# STM32F407IGH6BGA.net
KiCad netlist of a schematic drawn in Altium Designer
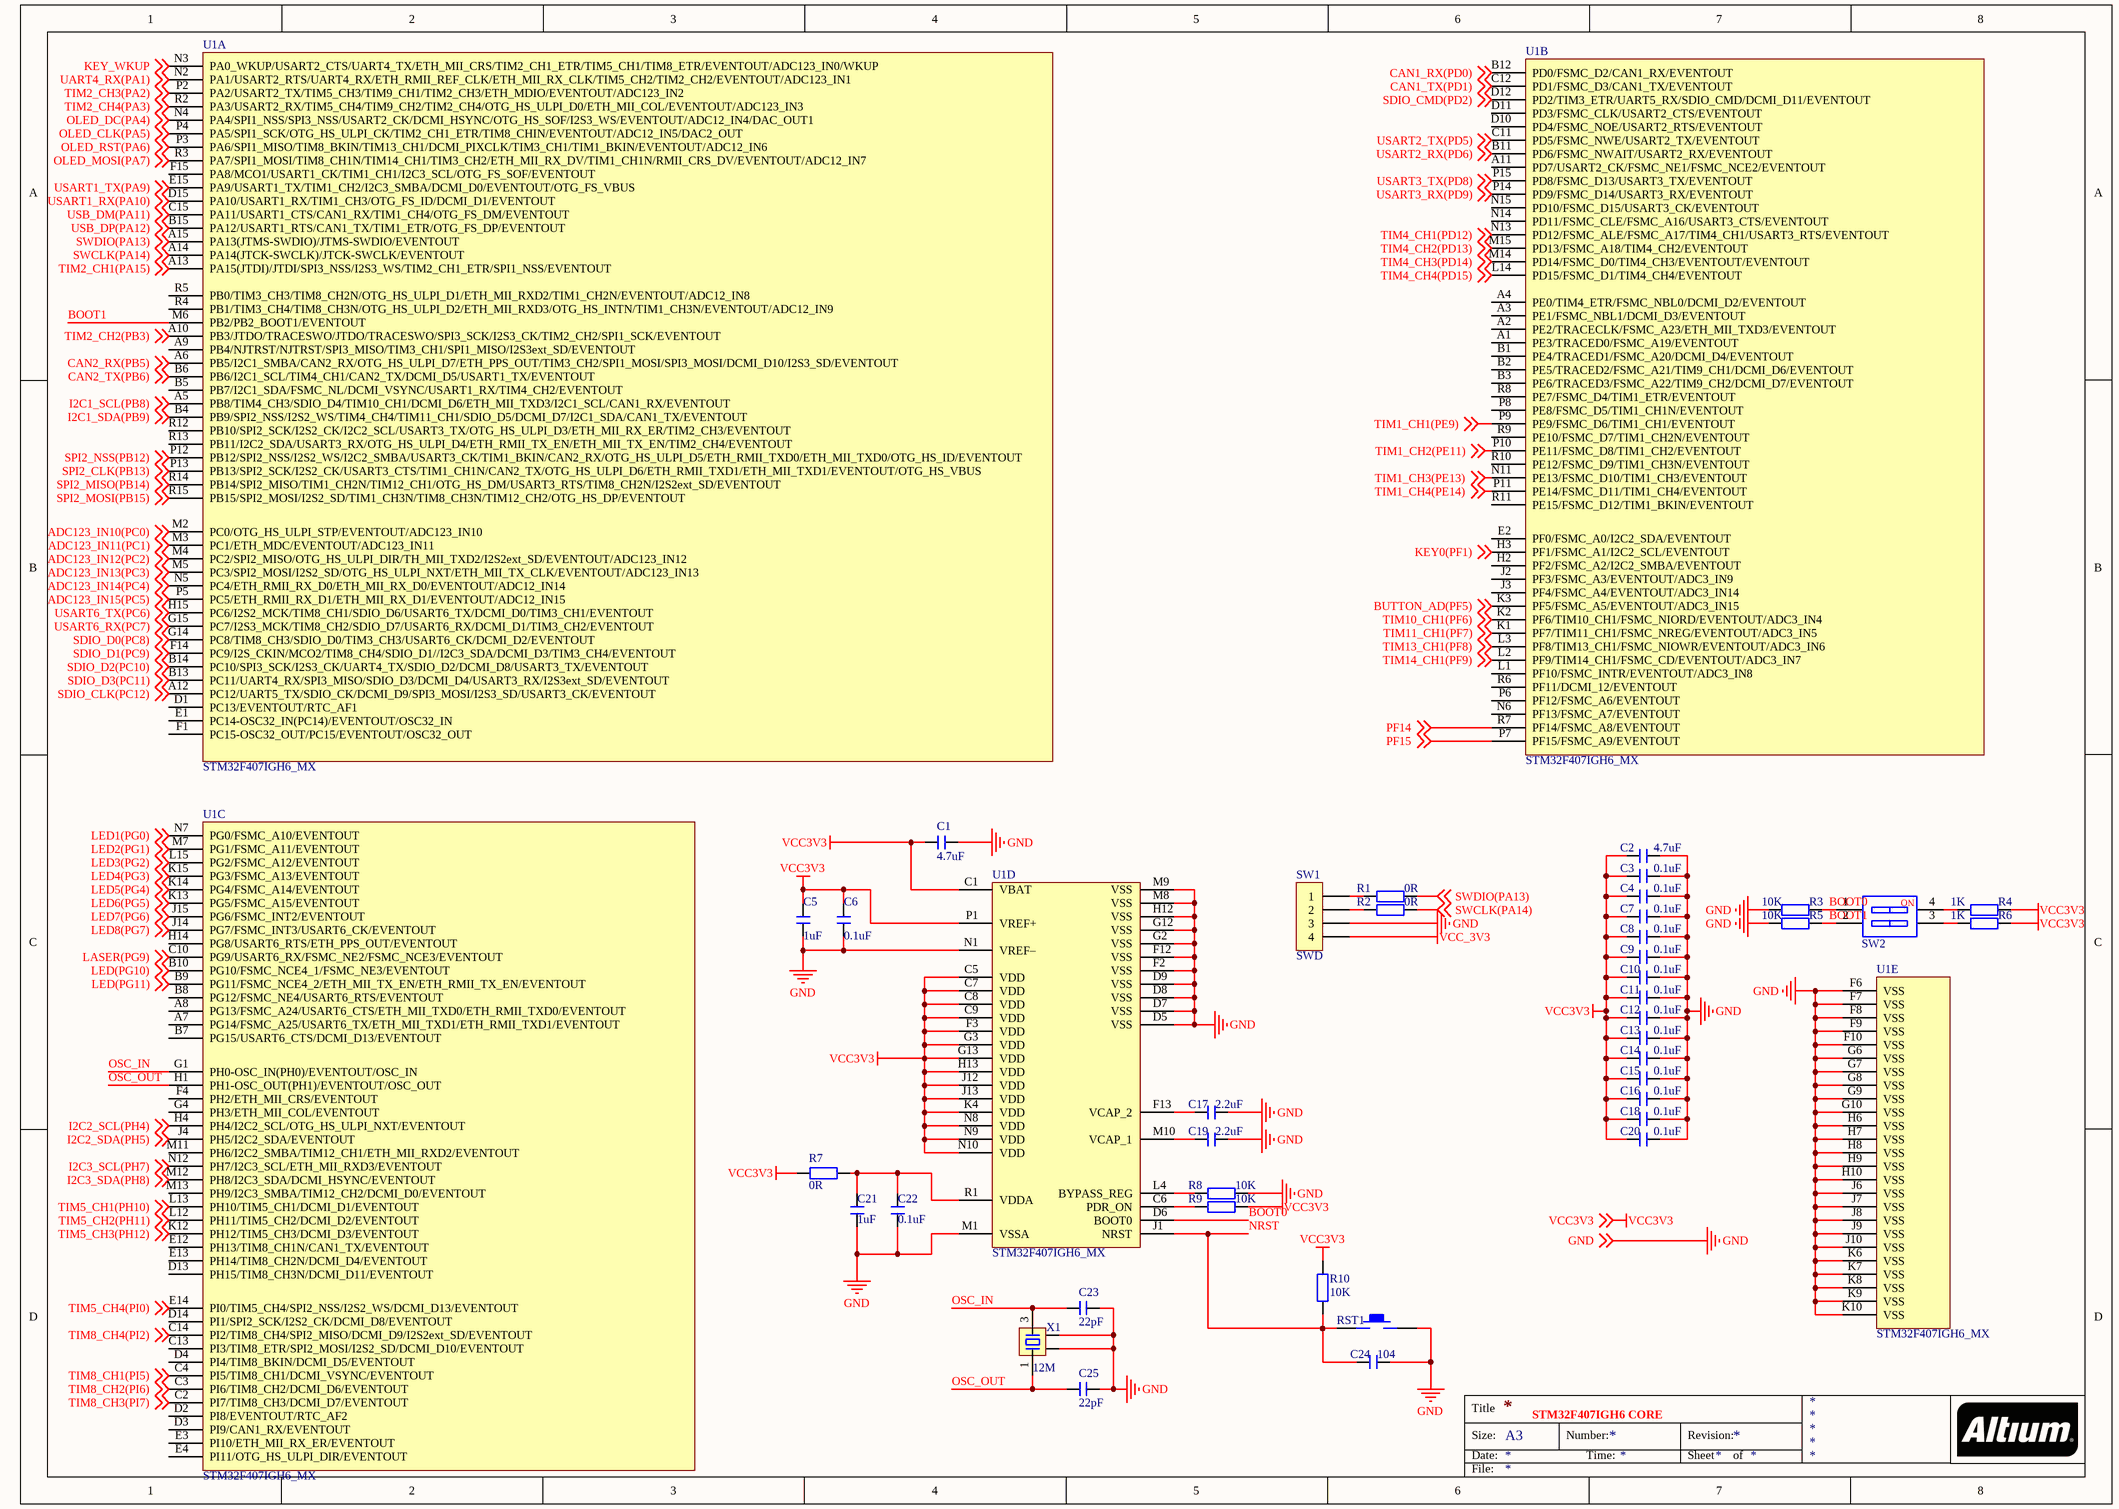
[diagram p0: STM32F407IGH6BGA.SchDoc]

(export (version "E")
  (design (tool "Eeschema 10.0.6"))
  (components
    (comp (ref "C1")
      (value "4.7uF")
      (footprint "C 0402_M")
      (description "贴片电容")
      (libsource (lib "0.1 - 电阻-电容-电感") (part "C"))
    )
    (comp (ref "C2")
      (value "4.7uF")
      (footprint "C 0402_M")
      (description "贴片电容")
      (libsource (lib "0.1 - 电阻-电容-电感") (part "C"))
    )
    (comp (ref "C3")
      (value "0.1uF")
      (footprint "C 0402_M")
      (description "贴片电容")
      (libsource (lib "0.1 - 电阻-电容-电感") (part "C"))
    )
    (comp (ref "C4")
      (value "0.1uF")
      (footprint "C 0402_M")
      (description "贴片电容")
      (libsource (lib "0.1 - 电阻-电容-电感") (part "C"))
    )
    (comp (ref "C5")
      (value "1uF")
      (footprint "C 0402_M")
      (description "贴片电容")
      (libsource (lib "0.1 - 电阻-电容-电感") (part "C"))
    )
    (comp (ref "C6")
      (value "0.1uF")
      (footprint "C 0402_M")
      (description "贴片电容")
      (libsource (lib "0.1 - 电阻-电容-电感") (part "C"))
    )
    (comp (ref "C7")
      (value "0.1uF")
      (footprint "C 0402_M")
      (description "贴片电容")
      (libsource (lib "0.1 - 电阻-电容-电感") (part "C"))
    )
    (comp (ref "C8")
      (value "0.1uF")
      (footprint "C 0402_M")
      (description "贴片电容")
      (libsource (lib "0.1 - 电阻-电容-电感") (part "C"))
    )
    (comp (ref "C9")
      (value "0.1uF")
      (footprint "C 0402_M")
      (description "贴片电容")
      (libsource (lib "0.1 - 电阻-电容-电感") (part "C"))
    )
    (comp (ref "C10")
      (value "0.1uF")
      (footprint "C 0402_M")
      (description "贴片电容")
      (libsource (lib "0.1 - 电阻-电容-电感") (part "C"))
    )
    (comp (ref "C11")
      (value "0.1uF")
      (footprint "C 0402_M")
      (description "贴片电容")
      (libsource (lib "0.1 - 电阻-电容-电感") (part "C"))
    )
    (comp (ref "C12")
      (value "0.1uF")
      (footprint "C 0402_M")
      (description "贴片电容")
      (libsource (lib "0.1 - 电阻-电容-电感") (part "C"))
    )
    (comp (ref "C13")
      (value "0.1uF")
      (footprint "C 0402_M")
      (description "贴片电容")
      (libsource (lib "0.1 - 电阻-电容-电感") (part "C"))
    )
    (comp (ref "C14")
      (value "0.1uF")
      (footprint "C 0402_M")
      (description "贴片电容")
      (libsource (lib "0.1 - 电阻-电容-电感") (part "C"))
    )
    (comp (ref "C15")
      (value "0.1uF")
      (footprint "C 0402_M")
      (description "贴片电容")
      (libsource (lib "0.1 - 电阻-电容-电感") (part "C"))
    )
    (comp (ref "C16")
      (value "0.1uF")
      (footprint "C 0402_M")
      (description "贴片电容")
      (libsource (lib "0.1 - 电阻-电容-电感") (part "C"))
    )
    (comp (ref "C17")
      (value "2.2uF")
      (footprint "C 0402_M")
      (description "贴片电容")
      (libsource (lib "0.1 - 电阻-电容-电感") (part "C"))
    )
    (comp (ref "C18")
      (value "0.1uF")
      (footprint "C 0402_M")
      (description "贴片电容")
      (libsource (lib "0.1 - 电阻-电容-电感") (part "C"))
    )
    (comp (ref "C19")
      (value "2.2uF")
      (footprint "C 0402_M")
      (description "贴片电容")
      (libsource (lib "0.1 - 电阻-电容-电感") (part "C"))
    )
    (comp (ref "C20")
      (value "0.1uF")
      (footprint "C 0402_M")
      (description "贴片电容")
      (libsource (lib "0.1 - 电阻-电容-电感") (part "C"))
    )
    (comp (ref "C21")
      (value "1uF")
      (footprint "C 0402_M")
      (description "贴片电容")
      (libsource (lib "0.1 - 电阻-电容-电感") (part "C"))
    )
    (comp (ref "C22")
      (value "0.1uF")
      (footprint "C 0402_M")
      (description "贴片电容")
      (libsource (lib "0.1 - 电阻-电容-电感") (part "C"))
    )
    (comp (ref "C23")
      (value "22pF")
      (footprint "C 0402_M")
      (description "贴片电容")
      (libsource (lib "0.1 - 电阻-电容-电感") (part "C"))
    )
    (comp (ref "C24")
      (value "104")
      (footprint "C 0402_M")
      (description "贴片电容")
      (libsource (lib "0.1 - 电阻-电容-电感") (part "C"))
    )
    (comp (ref "C25")
      (value "22pF")
      (footprint "C 0402_M")
      (description "贴片电容")
      (libsource (lib "0.1 - 电阻-电容-电感") (part "C"))
    )
    (comp (ref "R1")
      (value "0R")
      (footprint "R 0402_M")
      (description "贴片电阻")
      (libsource (lib "0.1 - 电阻-电容-电感") (part "R"))
    )
    (comp (ref "R2")
      (value "0R")
      (footprint "R 0402_M")
      (description "贴片电阻")
      (libsource (lib "0.1 - 电阻-电容-电感") (part "R"))
    )
    (comp (ref "R3")
      (value "10K")
      (footprint "R 0402_M")
      (description "贴片电阻")
      (libsource (lib "0.1 - 电阻-电容-电感") (part "R"))
    )
    (comp (ref "R4")
      (value "1K")
      (footprint "R 0402_M")
      (description "贴片电阻")
      (libsource (lib "0.1 - 电阻-电容-电感") (part "R"))
    )
    (comp (ref "R5")
      (value "10K")
      (footprint "R 0402_M")
      (description "贴片电阻")
      (libsource (lib "0.1 - 电阻-电容-电感") (part "R"))
    )
    (comp (ref "R6")
      (value "1K")
      (footprint "R 0402_M")
      (description "贴片电阻")
      (libsource (lib "0.1 - 电阻-电容-电感") (part "R"))
    )
    (comp (ref "R7")
      (value "0R")
      (footprint "R 0402_M")
      (description "贴片电阻")
      (libsource (lib "0.1 - 电阻-电容-电感") (part "R"))
    )
    (comp (ref "R8")
      (value "10K")
      (footprint "R 0402_M")
      (description "贴片电阻")
      (libsource (lib "0.1 - 电阻-电容-电感") (part "R"))
    )
    (comp (ref "R9")
      (value "10K")
      (footprint "R 0402_M")
      (description "贴片电阻")
      (libsource (lib "0.1 - 电阻-电容-电感") (part "R"))
    )
    (comp (ref "R10")
      (value "10K")
      (footprint "R 0402_M")
      (description "贴片电阻")
      (libsource (lib "0.1 - 电阻-电容-电感") (part "R"))
    )
    (comp (ref "RST1")
      (value "RST")
      (footprint "mx_pcb_library:SMD-3.2*4.2")
      (libsource (lib "mx_pcb_library") (part "KEY_M"))
    )
    (comp (ref "SW1")
      (value "SWD")
      (footprint "4.50-MX1.25连接器:MX 1.25-WS-4P")
      (description "Connector")
      (libsource (lib "mx_pcb_library") (part "HDR1x4"))
    )
    (comp (ref "SW2")
      (value "SW-2P")
      (footprint "CSW1.27 SMD-2P")
      (description "2路编码开关")
      (libsource (lib "0.7 - 常用按键-开关") (part "SW-2P"))
    )
    (comp (ref "U1")
      (value "STM32F407IGH6_MX")
      (footprint "mx_pcb_library:UBGA-176+25")
      (libsource (lib "mx_pcb_library") (part "STM32F407IGH6_MX"))
    )
    (comp (ref "X1")
      (value "12M")
      (footprint "OSC 3225-4P")
      (description "4脚无源晶振")
      (libsource (lib "2.0 - 保险丝-晶振-光耦") (part "XTAL-4P"))
    )
  )
  (nets
    (net (code "1") (name "/BOOT0") (class "Default")
      (node (ref "R3") (pin "2") (pinfunction "2_2") (pintype "passive"))
      (node (ref "SW2") (pin "1") (pinfunction "1_1") (pintype "passive"))
      (node (ref "U1") (pin "D6") (pinfunction "BOOT0_D6") (pintype "passive"))
    )
    (net (code "2") (name "/BOOT1") (class "Default")
      (node (ref "R5") (pin "2") (pinfunction "2_2") (pintype "passive"))
      (node (ref "SW2") (pin "2") (pinfunction "2_2") (pintype "passive"))
      (node (ref "U1") (pin "M6") (pinfunction "PB2/PB2_BOOT1/EVENTOUT_M6") (pintype "passive"))
    )
    (net (code "3") (name "/NRST") (class "Default")
      (node (ref "C24") (pin "1") (pinfunction "1_1") (pintype "passive"))
      (node (ref "R10") (pin "1") (pinfunction "1_1") (pintype "passive"))
      (node (ref "RST1") (pin "1") (pinfunction "1_1") (pintype "passive"))
      (node (ref "U1") (pin "J1") (pinfunction "NRST_J1") (pintype "passive"))
    )
    (net (code "4") (name "/OSC_IN") (class "Default")
      (node (ref "C23") (pin "1") (pinfunction "1_1") (pintype "passive"))
      (node (ref "U1") (pin "G1") (pinfunction "PH0-OSC_IN(PH0)/EVENTOUT/OSC_IN_G1") (pintype "passive"))
      (node (ref "X1") (pin "3") (pinfunction "3_3") (pintype "passive"))
    )
    (net (code "5") (name "/OSC_OUT") (class "Default")
      (node (ref "C25") (pin "1") (pinfunction "1_1") (pintype "passive"))
      (node (ref "U1") (pin "H1") (pinfunction "PH1-OSC_OUT(PH1)/EVENTOUT/OSC_OUT_H1") (pintype "passive"))
      (node (ref "X1") (pin "1") (pinfunction "1_1") (pintype "passive"))
    )
    (net (code "6") (name "ADC123_IN10(PC0)") (class "Default")
      (node (ref "U1") (pin "M2") (pinfunction "PC0/OTG_HS_ULPI_STP/EVENTOUT/ADC123_IN10_M2") (pintype "passive"))
    )
    (net (code "7") (name "ADC123_IN11(PC1)") (class "Default")
      (node (ref "U1") (pin "M3") (pinfunction "PC1/ETH_MDC/EVENTOUT/ADC123_IN11_M3") (pintype "passive"))
    )
    (net (code "8") (name "ADC123_IN12(PC2)") (class "Default")
      (node (ref "U1") (pin "M4") (pinfunction "PC2/SPI2_MISO/OTG_HS_ULPI_DIR/TH_MII_TXD2/I2S2ext_SD/EVENTOUT/ADC123_IN12_M4") (pintype "passive"))
    )
    (net (code "9") (name "ADC123_IN13(PC3)") (class "Default")
      (node (ref "U1") (pin "M5") (pinfunction "PC3/SPI2_MOSI/I2S2_SD/OTG_HS_ULPI_NXT/ETH_MII_TX_CLK/EVENTOUT/ADC123_IN13_M5") (pintype "passive"))
    )
    (net (code "10") (name "ADC123_IN14(PC4)") (class "Default")
      (node (ref "U1") (pin "N5") (pinfunction "PC4/ETH_RMII_RX_D0/ETH_MII_RX_D0/EVENTOUT/ADC12_IN14_N5") (pintype "passive"))
    )
    (net (code "11") (name "ADC123_IN15(PC5)") (class "Default")
      (node (ref "U1") (pin "P5") (pinfunction "PC5/ETH_RMII_RX_D1/ETH_MII_RX_D1/EVENTOUT/ADC12_IN15_P5") (pintype "passive"))
    )
    (net (code "12") (name "BUTTON_AD(PF5)") (class "Default")
      (node (ref "U1") (pin "K3") (pinfunction "PF5/FSMC_A5/EVENTOUT/ADC3_IN15_K3") (pintype "passive"))
    )
    (net (code "13") (name "CAN1_RX(PD0)") (class "Default")
      (node (ref "U1") (pin "B12") (pinfunction "PD0/FSMC_D2/CAN1_RX/EVENTOUT_B12") (pintype "passive"))
    )
    (net (code "14") (name "CAN1_TX(PD1)") (class "Default")
      (node (ref "U1") (pin "C12") (pinfunction "PD1/FSMC_D3/CAN1_TX/EVENTOUT_C12") (pintype "passive"))
    )
    (net (code "15") (name "CAN2_RX(PB5)") (class "Default")
      (node (ref "U1") (pin "A6") (pinfunction "PB5/I2C1_SMBA/CAN2_RX/OTG_HS_ULPI_D7/ETH_PPS_OUT/TIM3_CH2/SPI1_MOSI/SPI3_MOSI/DCMI_D10/I2S3_SD/EVENTOUT_A6") (pintype "passive"))
    )
    (net (code "16") (name "CAN2_TX(PB6)") (class "Default")
      (node (ref "U1") (pin "B6") (pinfunction "PB6/I2C1_SCL/TIM4_CH1/CAN2_TX/DCMI_D5/USART1_TX/EVENTOUT_B6") (pintype "passive"))
    )
    (net (code "17") (name "GND") (class "Default")
      (node (ref "C1") (pin "1") (pinfunction "1_1") (pintype "passive"))
      (node (ref "C10") (pin "2") (pinfunction "2_2") (pintype "passive"))
      (node (ref "C11") (pin "2") (pinfunction "2_2") (pintype "passive"))
      (node (ref "C12") (pin "2") (pinfunction "2_2") (pintype "passive"))
      (node (ref "C13") (pin "2") (pinfunction "2_2") (pintype "passive"))
      (node (ref "C14") (pin "2") (pinfunction "2_2") (pintype "passive"))
      (node (ref "C15") (pin "2") (pinfunction "2_2") (pintype "passive"))
      (node (ref "C16") (pin "2") (pinfunction "2_2") (pintype "passive"))
      (node (ref "C17") (pin "2") (pinfunction "2_2") (pintype "passive"))
      (node (ref "C18") (pin "2") (pinfunction "2_2") (pintype "passive"))
      (node (ref "C19") (pin "2") (pinfunction "2_2") (pintype "passive"))
      (node (ref "C2") (pin "2") (pinfunction "2_2") (pintype "passive"))
      (node (ref "C20") (pin "2") (pinfunction "2_2") (pintype "passive"))
      (node (ref "C21") (pin "1") (pinfunction "1_1") (pintype "passive"))
      (node (ref "C22") (pin "1") (pinfunction "1_1") (pintype "passive"))
      (node (ref "C23") (pin "2") (pinfunction "2_2") (pintype "passive"))
      (node (ref "C24") (pin "2") (pinfunction "2_2") (pintype "passive"))
      (node (ref "C25") (pin "2") (pinfunction "2_2") (pintype "passive"))
      (node (ref "C3") (pin "2") (pinfunction "2_2") (pintype "passive"))
      (node (ref "C4") (pin "2") (pinfunction "2_2") (pintype "passive"))
      (node (ref "C5") (pin "1") (pinfunction "1_1") (pintype "passive"))
      (node (ref "C6") (pin "1") (pinfunction "1_1") (pintype "passive"))
      (node (ref "C7") (pin "2") (pinfunction "2_2") (pintype "passive"))
      (node (ref "C8") (pin "2") (pinfunction "2_2") (pintype "passive"))
      (node (ref "C9") (pin "2") (pinfunction "2_2") (pintype "passive"))
      (node (ref "R3") (pin "1") (pinfunction "1_1") (pintype "passive"))
      (node (ref "R5") (pin "1") (pinfunction "1_1") (pintype "passive"))
      (node (ref "R8") (pin "2") (pinfunction "2_2") (pintype "passive"))
      (node (ref "RST1") (pin "2") (pinfunction "2_2") (pintype "passive"))
      (node (ref "SW1") (pin "3") (pinfunction "3_3") (pintype "passive"))
      (node (ref "U1") (pin "D5") (pinfunction "VSS_D5") (pintype "passive"))
      (node (ref "U1") (pin "D7") (pinfunction "VSS_D7") (pintype "passive"))
      (node (ref "U1") (pin "D8") (pinfunction "VSS_D8") (pintype "passive"))
      (node (ref "U1") (pin "D9") (pinfunction "VSS_D9") (pintype "passive"))
      (node (ref "U1") (pin "F10") (pinfunction "VSS_F10") (pintype "passive"))
      (node (ref "U1") (pin "F12") (pinfunction "VSS_F12") (pintype "passive"))
      (node (ref "U1") (pin "F2") (pinfunction "VSS_F2") (pintype "passive"))
      (node (ref "U1") (pin "F6") (pinfunction "VSS_F6") (pintype "passive"))
      (node (ref "U1") (pin "F7") (pinfunction "VSS_F7") (pintype "passive"))
      (node (ref "U1") (pin "F8") (pinfunction "VSS_F8") (pintype "passive"))
      (node (ref "U1") (pin "F9") (pinfunction "VSS_F9") (pintype "passive"))
      (node (ref "U1") (pin "G10") (pinfunction "VSS_G10") (pintype "passive"))
      (node (ref "U1") (pin "G12") (pinfunction "VSS_G12") (pintype "passive"))
      (node (ref "U1") (pin "G2") (pinfunction "VSS_G2") (pintype "passive"))
      (node (ref "U1") (pin "G6") (pinfunction "VSS_G6") (pintype "passive"))
      (node (ref "U1") (pin "G7") (pinfunction "VSS_G7") (pintype "passive"))
      (node (ref "U1") (pin "G8") (pinfunction "VSS_G8") (pintype "passive"))
      (node (ref "U1") (pin "G9") (pinfunction "VSS_G9") (pintype "passive"))
      (node (ref "U1") (pin "H10") (pinfunction "VSS_H10") (pintype "passive"))
      (node (ref "U1") (pin "H12") (pinfunction "VSS_H12") (pintype "passive"))
      (node (ref "U1") (pin "H6") (pinfunction "VSS_H6") (pintype "passive"))
      (node (ref "U1") (pin "H7") (pinfunction "VSS_H7") (pintype "passive"))
      (node (ref "U1") (pin "H8") (pinfunction "VSS_H8") (pintype "passive"))
      (node (ref "U1") (pin "H9") (pinfunction "VSS_H9") (pintype "passive"))
      (node (ref "U1") (pin "J10") (pinfunction "VSS_J10") (pintype "passive"))
      (node (ref "U1") (pin "J6") (pinfunction "VSS_J6") (pintype "passive"))
      (node (ref "U1") (pin "J7") (pinfunction "VSS_J7") (pintype "passive"))
      (node (ref "U1") (pin "J8") (pinfunction "VSS_J8") (pintype "passive"))
      (node (ref "U1") (pin "J9") (pinfunction "VSS_J9") (pintype "passive"))
      (node (ref "U1") (pin "K10") (pinfunction "VSS_K10") (pintype "passive"))
      (node (ref "U1") (pin "K6") (pinfunction "VSS_K6") (pintype "passive"))
      (node (ref "U1") (pin "K7") (pinfunction "VSS_K7") (pintype "passive"))
      (node (ref "U1") (pin "K8") (pinfunction "VSS_K8") (pintype "passive"))
      (node (ref "U1") (pin "K9") (pinfunction "VSS_K9") (pintype "passive"))
      (node (ref "U1") (pin "M1") (pinfunction "VSSA_M1") (pintype "passive"))
      (node (ref "U1") (pin "M8") (pinfunction "VSS_M8") (pintype "passive"))
      (node (ref "U1") (pin "M9") (pinfunction "VSS_M9") (pintype "passive"))
      (node (ref "U1") (pin "N1") (pinfunction "VREF–_N1") (pintype "passive"))
      (node (ref "X1") (pin "2") (pinfunction "2_2") (pintype "passive"))
      (node (ref "X1") (pin "4") (pinfunction "4_4") (pintype "passive"))
    )
    (net (code "18") (name "I2C1_SCL(PB8)") (class "Default")
      (node (ref "U1") (pin "A5") (pinfunction "PB8/TIM4_CH3/SDIO_D4/TIM10_CH1/DCMI_D6/ETH_MII_TXD3/I2C1_SCL/CAN1_RX/EVENTOUT_A5") (pintype "passive"))
    )
    (net (code "19") (name "I2C1_SDA(PB9)") (class "Default")
      (node (ref "U1") (pin "B4") (pinfunction "PB9/SPI2_NSS/I2S2_WS/TIM4_CH4/TIM11_CH1/SDIO_D5/DCMI_D7/I2C1_SDA/CAN1_TX/EVENTOUT_B4") (pintype "passive"))
    )
    (net (code "20") (name "I2C2_SCL(PH4)") (class "Default")
      (node (ref "U1") (pin "H4") (pinfunction "PH4/I2C2_SCL/OTG_HS_ULPI_NXT/EVENTOUT_H4") (pintype "passive"))
    )
    (net (code "21") (name "I2C2_SDA(PH5)") (class "Default")
      (node (ref "U1") (pin "J4") (pinfunction "PH5/I2C2_SDA/EVENTOUT_J4") (pintype "passive"))
    )
    (net (code "22") (name "I2C3_SCL(PH7)") (class "Default")
      (node (ref "U1") (pin "N12") (pinfunction "PH7/I2C3_SCL/ETH_MII_RXD3/EVENTOUT_N12") (pintype "passive"))
    )
    (net (code "23") (name "I2C3_SDA(PH8)") (class "Default")
      (node (ref "U1") (pin "M12") (pinfunction "PH8/I2C3_SDA/DCMI_HSYNC/EVENTOUT_M12") (pintype "passive"))
    )
    (net (code "24") (name "KEY0(PF1)") (class "Default")
      (node (ref "U1") (pin "H3") (pinfunction "PF1/FSMC_A1/I2C2_SCL/EVENTOUT_H3") (pintype "passive"))
    )
    (net (code "25") (name "KEY_WKUP") (class "Default")
      (node (ref "U1") (pin "N3") (pinfunction "PA0_WKUP/USART2_CTS/UART4_TX/ETH_MII_CRS/TIM2_CH1_ETR/TIM5_CH1/TIM8_ETR/EVENTOUT/ADC123_IN0/WKUP_N3") (pintype "passive"))
    )
    (net (code "26") (name "LASER(PG9)") (class "Default")
      (node (ref "U1") (pin "C10") (pinfunction "PG9/USART6_RX/FSMC_NE2/FSMC_NCE3/EVENTOUT_C10") (pintype "passive"))
    )
    (net (code "27") (name "LED(PG10)") (class "Default")
      (node (ref "U1") (pin "B10") (pinfunction "PG10/FSMC_NCE4_1/FSMC_NE3/EVENTOUT_B10") (pintype "passive"))
    )
    (net (code "28") (name "LED(PG11)") (class "Default")
      (node (ref "U1") (pin "B9") (pinfunction "PG11/FSMC_NCE4_2/ETH_MII_TX_EN/ETH_RMII_TX_EN/EVENTOUT_B9") (pintype "passive"))
    )
    (net (code "29") (name "LED1(PG0)") (class "Default")
      (node (ref "U1") (pin "N7") (pinfunction "PG0/FSMC_A10/EVENTOUT_N7") (pintype "passive"))
    )
    (net (code "30") (name "LED2(PG1)") (class "Default")
      (node (ref "U1") (pin "M7") (pinfunction "PG1/FSMC_A11/EVENTOUT_M7") (pintype "passive"))
    )
    (net (code "31") (name "LED3(PG2)") (class "Default")
      (node (ref "U1") (pin "L15") (pinfunction "PG2/FSMC_A12/EVENTOUT_L15") (pintype "passive"))
    )
    (net (code "32") (name "LED4(PG3)") (class "Default")
      (node (ref "U1") (pin "K15") (pinfunction "PG3/FSMC_A13/EVENTOUT_K15") (pintype "passive"))
    )
    (net (code "33") (name "LED5(PG4)") (class "Default")
      (node (ref "U1") (pin "K14") (pinfunction "PG4/FSMC_A14/EVENTOUT_K14") (pintype "passive"))
    )
    (net (code "34") (name "LED6(PG5)") (class "Default")
      (node (ref "U1") (pin "K13") (pinfunction "PG5/FSMC_A15/EVENTOUT_K13") (pintype "passive"))
    )
    (net (code "35") (name "LED7(PG6)") (class "Default")
      (node (ref "U1") (pin "J15") (pinfunction "PG6/FSMC_INT2/EVENTOUT_J15") (pintype "passive"))
    )
    (net (code "36") (name "LED8(PG7)") (class "Default")
      (node (ref "U1") (pin "J14") (pinfunction "PG7/FSMC_INT3/USART6_CK/EVENTOUT_J14") (pintype "passive"))
    )
    (net (code "37") (name "Net-(R1-Pad1)") (class "Default")
      (node (ref "R1") (pin "1") (pinfunction "1_1") (pintype "passive"))
      (node (ref "SW1") (pin "1") (pinfunction "1_1") (pintype "passive"))
    )
    (net (code "38") (name "Net-(R2-Pad1)") (class "Default")
      (node (ref "R2") (pin "1") (pinfunction "1_1") (pintype "passive"))
      (node (ref "SW1") (pin "2") (pinfunction "2_2") (pintype "passive"))
    )
    (net (code "39") (name "Net-(R4-Pad1)") (class "Default")
      (node (ref "R4") (pin "1") (pinfunction "1_1") (pintype "passive"))
      (node (ref "SW2") (pin "4") (pinfunction "4_4") (pintype "passive"))
    )
    (net (code "40") (name "Net-(R6-Pad1)") (class "Default")
      (node (ref "R6") (pin "1") (pinfunction "1_1") (pintype "passive"))
      (node (ref "SW2") (pin "3") (pinfunction "3_3") (pintype "passive"))
    )
    (net (code "41") (name "Net-(U1D-BYPASS_REG)") (class "Default")
      (node (ref "R8") (pin "1") (pinfunction "1_1") (pintype "passive"))
      (node (ref "U1") (pin "L4") (pinfunction "BYPASS_REG_L4") (pintype "passive"))
    )
    (net (code "42") (name "Net-(U1D-PDR_ON)") (class "Default")
      (node (ref "R9") (pin "1") (pinfunction "1_1") (pintype "passive"))
      (node (ref "U1") (pin "C6") (pinfunction "PDR_ON_C6") (pintype "passive"))
    )
    (net (code "43") (name "Net-(U1D-VCAP_1)") (class "Default")
      (node (ref "C19") (pin "1") (pinfunction "1_1") (pintype "passive"))
      (node (ref "U1") (pin "M10") (pinfunction "VCAP_1_M10") (pintype "passive"))
    )
    (net (code "44") (name "Net-(U1D-VCAP_2)") (class "Default")
      (node (ref "C17") (pin "1") (pinfunction "1_1") (pintype "passive"))
      (node (ref "U1") (pin "F13") (pinfunction "VCAP_2_F13") (pintype "passive"))
    )
    (net (code "45") (name "Net-(U1D-VDDA)") (class "Default")
      (node (ref "C21") (pin "2") (pinfunction "2_2") (pintype "passive"))
      (node (ref "C22") (pin "2") (pinfunction "2_2") (pintype "passive"))
      (node (ref "R7") (pin "2") (pinfunction "2_2") (pintype "passive"))
      (node (ref "U1") (pin "R1") (pinfunction "VDDA_R1") (pintype "passive"))
    )
    (net (code "46") (name "OLED_CLK(PA5)") (class "Default")
      (node (ref "U1") (pin "P4") (pinfunction "PA5/SPI1_SCK/OTG_HS_ULPI_CK/TIM2_CH1_ETR/TIM8_CHIN/EVENTOUT/ADC12_IN5/DAC2_OUT_P4") (pintype "passive"))
    )
    (net (code "47") (name "OLED_DC(PA4)") (class "Default")
      (node (ref "U1") (pin "N4") (pinfunction "PA4/SPI1_NSS/SPI3_NSS/USART2_CK/DCMI_HSYNC/OTG_HS_SOF/I2S3_WS/EVENTOUT/ADC12_IN4/DAC_OUT1_N4") (pintype "passive"))
    )
    (net (code "48") (name "OLED_MOSI(PA7)") (class "Default")
      (node (ref "U1") (pin "R3") (pinfunction "PA7/SPI1_MOSI/TIM8_CH1N/TIM14_CH1/TIM3_CH2/ETH_MII_RX_DV/TIM1_CH1N/RMII_CRS_DV/EVENTOUT/ADC12_IN7_R3") (pintype "passive"))
    )
    (net (code "49") (name "OLED_RST(PA6)") (class "Default")
      (node (ref "U1") (pin "P3") (pinfunction "PA6/SPI1_MISO/TIM8_BKIN/TIM13_CH1/DCMI_PIXCLK/TIM3_CH1/TIM1_BKIN/EVENTOUT/ADC12_IN6_P3") (pintype "passive"))
    )
    (net (code "50") (name "PF14") (class "Default")
      (node (ref "U1") (pin "R7") (pinfunction "PF14/FSMC_A8/EVENTOUT_R7") (pintype "passive"))
    )
    (net (code "51") (name "PF15") (class "Default")
      (node (ref "U1") (pin "P7") (pinfunction "PF15/FSMC_A9/EVENTOUT_P7") (pintype "passive"))
    )
    (net (code "52") (name "SDIO_CLK(PC12)") (class "Default")
      (node (ref "U1") (pin "A12") (pinfunction "PC12/UART5_TX/SDIO_CK/DCMI_D9/SPI3_MOSI/I2S3_SD/USART3_CK/EVENTOUT_A12") (pintype "passive"))
    )
    (net (code "53") (name "SDIO_CMD(PD2)") (class "Default")
      (node (ref "U1") (pin "D12") (pinfunction "PD2/TIM3_ETR/UART5_RX/SDIO_CMD/DCMI_D11/EVENTOUT_D12") (pintype "passive"))
    )
    (net (code "54") (name "SDIO_D0(PC8)") (class "Default")
      (node (ref "U1") (pin "G14") (pinfunction "PC8/TIM8_CH3/SDIO_D0/TIM3_CH3/USART6_CK/DCMI_D2/EVENTOUT_G14") (pintype "passive"))
    )
    (net (code "55") (name "SDIO_D1(PC9)") (class "Default")
      (node (ref "U1") (pin "F14") (pinfunction "PC9/I2S_CKIN/MCO2/TIM8_CH4/SDIO_D1//I2C3_SDA/DCMI_D3/TIM3_CH4/EVENTOUT_F14") (pintype "passive"))
    )
    (net (code "56") (name "SDIO_D2(PC10)") (class "Default")
      (node (ref "U1") (pin "B14") (pinfunction "PC10/SPI3_SCK/I2S3_CK/UART4_TX/SDIO_D2/DCMI_D8/USART3_TX/EVENTOUT_B14") (pintype "passive"))
    )
    (net (code "57") (name "SDIO_D3(PC11)") (class "Default")
      (node (ref "U1") (pin "B13") (pinfunction "PC11/UART4_RX/SPI3_MISO/SDIO_D3/DCMI_D4/USART3_RX/I2S3ext_SD/EVENTOUT_B13") (pintype "passive"))
    )
    (net (code "58") (name "SPI2_CLK(PB13)") (class "Default")
      (node (ref "U1") (pin "P13") (pinfunction "PB13/SPI2_SCK/I2S2_CK/USART3_CTS/TIM1_CH1N/CAN2_TX/OTG_HS_ULPI_D6/ETH_RMII_TXD1/ETH_MII_TXD1/EVENTOUT/OTG_HS_VBUS_P13") (pintype "passive"))
    )
    (net (code "59") (name "SPI2_MISO(PB14)") (class "Default")
      (node (ref "U1") (pin "R14") (pinfunction "PB14/SPI2_MISO/TIM1_CH2N/TIM12_CH1/OTG_HS_DM/USART3_RTS/TIM8_CH2N/I2S2ext_SD/EVENTOUT_R14") (pintype "passive"))
    )
    (net (code "60") (name "SPI2_MOSI(PB15)") (class "Default")
      (node (ref "U1") (pin "R15") (pinfunction "PB15/SPI2_MOSI/I2S2_SD/TIM1_CH3N/TIM8_CH3N/TIM12_CH2/OTG_HS_DP/EVENTOUT_R15") (pintype "passive"))
    )
    (net (code "61") (name "SPI2_NSS(PB12)") (class "Default")
      (node (ref "U1") (pin "P12") (pinfunction "PB12/SPI2_NSS/I2S2_WS/I2C2_SMBA/USART3_CK/TIM1_BKIN/CAN2_RX/OTG_HS_ULPI_D5/ETH_RMII_TXD0/ETH_MII_TXD0/OTG_HS_ID/EVENTOUT_P12") (pintype "passive"))
    )
    (net (code "62") (name "SWCLK(PA14)") (class "Default")
      (node (ref "R2") (pin "2") (pinfunction "2_2") (pintype "passive"))
      (node (ref "U1") (pin "A14") (pinfunction "PA14(JTCK-SWCLK)/JTCK-SWCLK/EVENTOUT_A14") (pintype "passive"))
    )
    (net (code "63") (name "SWDIO(PA13)") (class "Default")
      (node (ref "R1") (pin "2") (pinfunction "2_2") (pintype "passive"))
      (node (ref "U1") (pin "A15") (pinfunction "PA13(JTMS-SWDIO)/JTMS-SWDIO/EVENTOUT_A15") (pintype "passive"))
    )
    (net (code "64") (name "TIM1_CH1(PE9)") (class "Default")
      (node (ref "U1") (pin "P9") (pinfunction "PE9/FSMC_D6/TIM1_CH1/EVENTOUT_P9") (pintype "passive"))
    )
    (net (code "65") (name "TIM1_CH2(PE11)") (class "Default")
      (node (ref "U1") (pin "P10") (pinfunction "PE11/FSMC_D8/TIM1_CH2/EVENTOUT_P10") (pintype "passive"))
    )
    (net (code "66") (name "TIM1_CH3(PE13)") (class "Default")
      (node (ref "U1") (pin "N11") (pinfunction "PE13/FSMC_D10/TIM1_CH3/EVENTOUT_N11") (pintype "passive"))
    )
    (net (code "67") (name "TIM1_CH4(PE14)") (class "Default")
      (node (ref "U1") (pin "P11") (pinfunction "PE14/FSMC_D11/TIM1_CH4/EVENTOUT_P11") (pintype "passive"))
    )
    (net (code "68") (name "TIM2_CH1(PA15)") (class "Default")
      (node (ref "U1") (pin "A13") (pinfunction "PA15(JTDI)/JTDI/SPI3_NSS/I2S3_WS/TIM2_CH1_ETR/SPI1_NSS/EVENTOUT_A13") (pintype "passive"))
    )
    (net (code "69") (name "TIM2_CH2(PB3)") (class "Default")
      (node (ref "U1") (pin "A10") (pinfunction "PB3/JTDO/TRACESWO/JTDO/TRACESWO/SPI3_SCK/I2S3_CK/TIM2_CH2/SPI1_SCK/EVENTOUT_A10") (pintype "passive"))
    )
    (net (code "70") (name "TIM2_CH3(PA2)") (class "Default")
      (node (ref "U1") (pin "P2") (pinfunction "PA2/USART2_TX/TIM5_CH3/TIM9_CH1/TIM2_CH3/ETH_MDIO/EVENTOUT/ADC123_IN2_P2") (pintype "passive"))
    )
    (net (code "71") (name "TIM2_CH4(PA3)") (class "Default")
      (node (ref "U1") (pin "R2") (pinfunction "PA3/USART2_RX/TIM5_CH4/TIM9_CH2/TIM2_CH4/OTG_HS_ULPI_D0/ETH_MII_COL/EVENTOUT/ADC123_IN3_R2") (pintype "passive"))
    )
    (net (code "72") (name "TIM4_CH1(PD12)") (class "Default")
      (node (ref "U1") (pin "N13") (pinfunction "PD12/FSMC_ALE/FSMC_A17/TIM4_CH1/USART3_RTS/EVENTOUT_N13") (pintype "passive"))
    )
    (net (code "73") (name "TIM4_CH2(PD13)") (class "Default")
      (node (ref "U1") (pin "M15") (pinfunction "PD13/FSMC_A18/TIM4_CH2/EVENTOUT_M15") (pintype "passive"))
    )
    (net (code "74") (name "TIM4_CH3(PD14)") (class "Default")
      (node (ref "U1") (pin "M14") (pinfunction "PD14/FSMC_D0/TIM4_CH3/EVENTOUT/EVENTOUT_M14") (pintype "passive"))
    )
    (net (code "75") (name "TIM4_CH4(PD15)") (class "Default")
      (node (ref "U1") (pin "L14") (pinfunction "PD15/FSMC_D1/TIM4_CH4/EVENTOUT_L14") (pintype "passive"))
    )
    (net (code "76") (name "TIM5_CH1(PH10)") (class "Default")
      (node (ref "U1") (pin "L13") (pinfunction "PH10/TIM5_CH1/DCMI_D1/EVENTOUT_L13") (pintype "passive"))
    )
    (net (code "77") (name "TIM5_CH2(PH11)") (class "Default")
      (node (ref "U1") (pin "L12") (pinfunction "PH11/TIM5_CH2/DCMI_D2/EVENTOUT_L12") (pintype "passive"))
    )
    (net (code "78") (name "TIM5_CH3(PH12)") (class "Default")
      (node (ref "U1") (pin "K12") (pinfunction "PH12/TIM5_CH3/DCMI_D3/EVENTOUT_K12") (pintype "passive"))
    )
    (net (code "79") (name "TIM5_CH4(PI0)") (class "Default")
      (node (ref "U1") (pin "E14") (pinfunction "PI0/TIM5_CH4/SPI2_NSS/I2S2_WS/DCMI_D13/EVENTOUT_E14") (pintype "passive"))
    )
    (net (code "80") (name "TIM8_CH1(PI5)") (class "Default")
      (node (ref "U1") (pin "C4") (pinfunction "PI5/TIM8_CH1/DCMI_VSYNC/EVENTOUT_C4") (pintype "passive"))
    )
    (net (code "81") (name "TIM8_CH2(PI6)") (class "Default")
      (node (ref "U1") (pin "C3") (pinfunction "PI6/TIM8_CH2/DCMI_D6/EVENTOUT_C3") (pintype "passive"))
    )
    (net (code "82") (name "TIM8_CH3(PI7)") (class "Default")
      (node (ref "U1") (pin "C2") (pinfunction "PI7/TIM8_CH3/DCMI_D7/EVENTOUT_C2") (pintype "passive"))
    )
    (net (code "83") (name "TIM8_CH4(PI2)") (class "Default")
      (node (ref "U1") (pin "C14") (pinfunction "PI2/TIM8_CH4/SPI2_MISO/DCMI_D9/I2S2ext_SD/EVENTOUT_C14") (pintype "passive"))
    )
    (net (code "84") (name "TIM10_CH1(PF6)") (class "Default")
      (node (ref "U1") (pin "K2") (pinfunction "PF6/TIM10_CH1/FSMC_NIORD/EVENTOUT/ADC3_IN4_K2") (pintype "passive"))
    )
    (net (code "85") (name "TIM11_CH1(PF7)") (class "Default")
      (node (ref "U1") (pin "K1") (pinfunction "PF7/TIM11_CH1/FSMC_NREG/EVENTOUT/ADC3_IN5_K1") (pintype "passive"))
    )
    (net (code "86") (name "TIM13_CH1(PF8)") (class "Default")
      (node (ref "U1") (pin "L3") (pinfunction "PF8/TIM13_CH1/FSMC_NIOWR/EVENTOUT/ADC3_IN6_L3") (pintype "passive"))
    )
    (net (code "87") (name "TIM14_CH1(PF9)") (class "Default")
      (node (ref "U1") (pin "L2") (pinfunction "PF9/TIM14_CH1/FSMC_CD/EVENTOUT/ADC3_IN7_L2") (pintype "passive"))
    )
    (net (code "88") (name "UART4_RX(PA1)") (class "Default")
      (node (ref "U1") (pin "N2") (pinfunction "PA1/USART2_RTS/UART4_RX/ETH_RMII_REF_CLK/ETH_MII_RX_CLK/TIM5_CH2/TIM2_CH2/EVENTOUT/ADC123_IN1_N2") (pintype "passive"))
    )
    (net (code "89") (name "USART1_RX(PA10)") (class "Default")
      (node (ref "U1") (pin "D15") (pinfunction "PA10/USART1_RX/TIM1_CH3/OTG_FS_ID/DCMI_D1/EVENTOUT_D15") (pintype "passive"))
    )
    (net (code "90") (name "USART1_TX(PA9)") (class "Default")
      (node (ref "U1") (pin "E15") (pinfunction "PA9/USART1_TX/TIM1_CH2/I2C3_SMBA/DCMI_D0/EVENTOUT/OTG_FS_VBUS_E15") (pintype "passive"))
    )
    (net (code "91") (name "USART2_RX(PD6)") (class "Default")
      (node (ref "U1") (pin "B11") (pinfunction "PD6/FSMC_NWAIT/USART2_RX/EVENTOUT_B11") (pintype "passive"))
    )
    (net (code "92") (name "USART2_TX(PD5)") (class "Default")
      (node (ref "U1") (pin "C11") (pinfunction "PD5/FSMC_NWE/USART2_TX/EVENTOUT_C11") (pintype "passive"))
    )
    (net (code "93") (name "USART3_RX(PD9)") (class "Default")
      (node (ref "U1") (pin "P14") (pinfunction "PD9/FSMC_D14/USART3_RX/EVENTOUT_P14") (pintype "passive"))
    )
    (net (code "94") (name "USART3_TX(PD8)") (class "Default")
      (node (ref "U1") (pin "P15") (pinfunction "PD8/FSMC_D13/USART3_TX/EVENTOUT_P15") (pintype "passive"))
    )
    (net (code "95") (name "USART6_RX(PC7)") (class "Default")
      (node (ref "U1") (pin "G15") (pinfunction "PC7/I2S3_MCK/TIM8_CH2/SDIO_D7/USART6_RX/DCMI_D1/TIM3_CH2/EVENTOUT_G15") (pintype "passive"))
    )
    (net (code "96") (name "USART6_TX(PC6)") (class "Default")
      (node (ref "U1") (pin "H15") (pinfunction "PC6/I2S2_MCK/TIM8_CH1/SDIO_D6/USART6_TX/DCMI_D0/TIM3_CH1/EVENTOUT_H15") (pintype "passive"))
    )
    (net (code "97") (name "USB_DM(PA11)") (class "Default")
      (node (ref "U1") (pin "C15") (pinfunction "PA11/USART1_CTS/CAN1_RX/TIM1_CH4/OTG_FS_DM/EVENTOUT_C15") (pintype "passive"))
    )
    (net (code "98") (name "USB_DP(PA12)") (class "Default")
      (node (ref "U1") (pin "B15") (pinfunction "PA12/USART1_RTS/CAN1_TX/TIM1_ETR/OTG_FS_DP/EVENTOUT_B15") (pintype "passive"))
    )
    (net (code "99") (name "VCC3V3") (class "Default")
      (node (ref "C1") (pin "2") (pinfunction "2_2") (pintype "passive"))
      (node (ref "C10") (pin "1") (pinfunction "1_1") (pintype "passive"))
      (node (ref "C11") (pin "1") (pinfunction "1_1") (pintype "passive"))
      (node (ref "C12") (pin "1") (pinfunction "1_1") (pintype "passive"))
      (node (ref "C13") (pin "1") (pinfunction "1_1") (pintype "passive"))
      (node (ref "C14") (pin "1") (pinfunction "1_1") (pintype "passive"))
      (node (ref "C15") (pin "1") (pinfunction "1_1") (pintype "passive"))
      (node (ref "C16") (pin "1") (pinfunction "1_1") (pintype "passive"))
      (node (ref "C18") (pin "1") (pinfunction "1_1") (pintype "passive"))
      (node (ref "C2") (pin "1") (pinfunction "1_1") (pintype "passive"))
      (node (ref "C20") (pin "1") (pinfunction "1_1") (pintype "passive"))
      (node (ref "C3") (pin "1") (pinfunction "1_1") (pintype "passive"))
      (node (ref "C4") (pin "1") (pinfunction "1_1") (pintype "passive"))
      (node (ref "C5") (pin "2") (pinfunction "2_2") (pintype "passive"))
      (node (ref "C6") (pin "2") (pinfunction "2_2") (pintype "passive"))
      (node (ref "C7") (pin "1") (pinfunction "1_1") (pintype "passive"))
      (node (ref "C8") (pin "1") (pinfunction "1_1") (pintype "passive"))
      (node (ref "C9") (pin "1") (pinfunction "1_1") (pintype "passive"))
      (node (ref "R10") (pin "2") (pinfunction "2_2") (pintype "passive"))
      (node (ref "R4") (pin "2") (pinfunction "2_2") (pintype "passive"))
      (node (ref "R6") (pin "2") (pinfunction "2_2") (pintype "passive"))
      (node (ref "R7") (pin "1") (pinfunction "1_1") (pintype "passive"))
      (node (ref "R9") (pin "2") (pinfunction "2_2") (pintype "passive"))
      (node (ref "U1") (pin "C1") (pinfunction "VBAT_C1") (pintype "passive"))
      (node (ref "U1") (pin "C5") (pinfunction "VDD_C5") (pintype "passive"))
      (node (ref "U1") (pin "C7") (pinfunction "VDD_C7") (pintype "passive"))
      (node (ref "U1") (pin "C8") (pinfunction "VDD_C8") (pintype "passive"))
      (node (ref "U1") (pin "C9") (pinfunction "VDD_C9") (pintype "passive"))
      (node (ref "U1") (pin "F3") (pinfunction "VDD_F3") (pintype "passive"))
      (node (ref "U1") (pin "G13") (pinfunction "VDD_G13") (pintype "passive"))
      (node (ref "U1") (pin "G3") (pinfunction "VDD_G3") (pintype "passive"))
      (node (ref "U1") (pin "H13") (pinfunction "VDD_H13") (pintype "passive"))
      (node (ref "U1") (pin "J12") (pinfunction "VDD_J12") (pintype "passive"))
      (node (ref "U1") (pin "J13") (pinfunction "VDD_J13") (pintype "passive"))
      (node (ref "U1") (pin "K4") (pinfunction "VDD_K4") (pintype "passive"))
      (node (ref "U1") (pin "N10") (pinfunction "VDD_N10") (pintype "passive"))
      (node (ref "U1") (pin "N8") (pinfunction "VDD_N8") (pintype "passive"))
      (node (ref "U1") (pin "N9") (pinfunction "VDD_N9") (pintype "passive"))
      (node (ref "U1") (pin "P1") (pinfunction "VREF+_P1") (pintype "passive"))
    )
    (net (code "100") (name "VCC_3V3") (class "Default")
      (node (ref "SW1") (pin "4") (pinfunction "4_4") (pintype "passive"))
    )
    (net (code "101") (name "unconnected-(U1A-PA8{slash}MCO1{slash}USART1_CK{slash}TIM1_CH1{slash}I2C3_SCL{slash}OTG_FS_SOF{slash}EVENTOUT-PadF15)") (class "Default")
      (node (ref "U1") (pin "F15") (pinfunction "PA8/MCO1/USART1_CK/TIM1_CH1/I2C3_SCL/OTG_FS_SOF/EVENTOUT_F15") (pintype "passive"))
    )
    (net (code "102") (name "unconnected-(U1A-PB0{slash}TIM3_CH3{slash}TIM8_CH2N{slash}OTG_HS_ULPI_D1{slash}ETH_MII_RXD2{slash}TIM1_CH2N{slash}EVENTOUT{slash}ADC12_IN8-PadR5)") (class "Default")
      (node (ref "U1") (pin "R5") (pinfunction "PB0/TIM3_CH3/TIM8_CH2N/OTG_HS_ULPI_D1/ETH_MII_RXD2/TIM1_CH2N/EVENTOUT/ADC12_IN8_R5") (pintype "passive"))
    )
    (net (code "103") (name "unconnected-(U1A-PB1{slash}TIM3_CH4{slash}TIM8_CH3N{slash}OTG_HS_ULPI_D2{slash}ETH_MII_RXD3{slash}OTG_HS_INTN{slash}TIM1_CH3N{slash}EVENTOUT{slash}ADC12_IN9-PadR4)") (class "Default")
      (node (ref "U1") (pin "R4") (pinfunction "PB1/TIM3_CH4/TIM8_CH3N/OTG_HS_ULPI_D2/ETH_MII_RXD3/OTG_HS_INTN/TIM1_CH3N/EVENTOUT/ADC12_IN9_R4") (pintype "passive"))
    )
    (net (code "104") (name "unconnected-(U1A-PB4{slash}NJTRST{slash}NJTRST{slash}SPI3_MISO{slash}TIM3_CH1{slash}SPI1_MISO{slash}I2S3ext_SD{slash}EVENTOUT-PadA9)") (class "Default")
      (node (ref "U1") (pin "A9") (pinfunction "PB4/NJTRST/NJTRST/SPI3_MISO/TIM3_CH1/SPI1_MISO/I2S3ext_SD/EVENTOUT_A9") (pintype "passive"))
    )
    (net (code "105") (name "unconnected-(U1A-PB7{slash}I2C1_SDA{slash}FSMC_NL{slash}DCMI_VSYNC{slash}USART1_RX{slash}TIM4_CH2{slash}EVENTOUT-PadB5)") (class "Default")
      (node (ref "U1") (pin "B5") (pinfunction "PB7/I2C1_SDA/FSMC_NL/DCMI_VSYNC/USART1_RX/TIM4_CH2/EVENTOUT_B5") (pintype "passive"))
    )
    (net (code "106") (name "unconnected-(U1A-PB10{slash}SPI2_SCK{slash}I2S2_CK{slash}I2C2_SCL{slash}USART3_TX{slash}OTG_HS_ULPI_D3{slash}ETH_MII_RX_ER{slash}TIM2_CH3{slash}EVENTOUT-PadR12)") (class "Default")
      (node (ref "U1") (pin "R12") (pinfunction "PB10/SPI2_SCK/I2S2_CK/I2C2_SCL/USART3_TX/OTG_HS_ULPI_D3/ETH_MII_RX_ER/TIM2_CH3/EVENTOUT_R12") (pintype "passive"))
    )
    (net (code "107") (name "unconnected-(U1A-PB11{slash}I2C2_SDA{slash}USART3_RX{slash}OTG_HS_ULPI_D4{slash}ETH_RMII_TX_EN{slash}ETH_MII_TX_EN{slash}TIM2_CH4{slash}EVENTOUT-PadR13)") (class "Default")
      (node (ref "U1") (pin "R13") (pinfunction "PB11/I2C2_SDA/USART3_RX/OTG_HS_ULPI_D4/ETH_RMII_TX_EN/ETH_MII_TX_EN/TIM2_CH4/EVENTOUT_R13") (pintype "passive"))
    )
    (net (code "108") (name "unconnected-(U1A-PC13{slash}EVENTOUT{slash}RTC_AF1-PadD1)") (class "Default")
      (node (ref "U1") (pin "D1") (pinfunction "PC13/EVENTOUT/RTC_AF1_D1") (pintype "passive"))
    )
    (net (code "109") (name "unconnected-(U1A-PC14-OSC32_IN(PC14){slash}EVENTOUT{slash}OSC32_IN-PadE1)") (class "Default")
      (node (ref "U1") (pin "E1") (pinfunction "PC14-OSC32_IN(PC14)/EVENTOUT/OSC32_IN_E1") (pintype "passive"))
    )
    (net (code "110") (name "unconnected-(U1A-PC15-OSC32_OUT{slash}PC15{slash}EVENTOUT{slash}OSC32_OUT-PadF1)") (class "Default")
      (node (ref "U1") (pin "F1") (pinfunction "PC15-OSC32_OUT/PC15/EVENTOUT/OSC32_OUT_F1") (pintype "passive"))
    )
    (net (code "111") (name "unconnected-(U1B-PD3{slash}FSMC_CLK{slash}USART2_CTS{slash}EVENTOUT-PadD11)") (class "Default")
      (node (ref "U1") (pin "D11") (pinfunction "PD3/FSMC_CLK/USART2_CTS/EVENTOUT_D11") (pintype "passive"))
    )
    (net (code "112") (name "unconnected-(U1B-PD4{slash}FSMC_NOE{slash}USART2_RTS{slash}EVENTOUT-PadD10)") (class "Default")
      (node (ref "U1") (pin "D10") (pinfunction "PD4/FSMC_NOE/USART2_RTS/EVENTOUT_D10") (pintype "passive"))
    )
    (net (code "113") (name "unconnected-(U1B-PD7{slash}USART2_CK{slash}FSMC_NE1{slash}FSMC_NCE2{slash}EVENTOUT-PadA11)") (class "Default")
      (node (ref "U1") (pin "A11") (pinfunction "PD7/USART2_CK/FSMC_NE1/FSMC_NCE2/EVENTOUT_A11") (pintype "passive"))
    )
    (net (code "114") (name "unconnected-(U1B-PD10{slash}FSMC_D15{slash}USART3_CK{slash}EVENTOUT-PadN15)") (class "Default")
      (node (ref "U1") (pin "N15") (pinfunction "PD10/FSMC_D15/USART3_CK/EVENTOUT_N15") (pintype "passive"))
    )
    (net (code "115") (name "unconnected-(U1B-PD11{slash}FSMC_CLE{slash}FSMC_A16{slash}USART3_CTS{slash}EVENTOUT-PadN14)") (class "Default")
      (node (ref "U1") (pin "N14") (pinfunction "PD11/FSMC_CLE/FSMC_A16/USART3_CTS/EVENTOUT_N14") (pintype "passive"))
    )
    (net (code "116") (name "unconnected-(U1B-PE0{slash}TIM4_ETR{slash}FSMC_NBL0{slash}DCMI_D2{slash}EVENTOUT-PadA4)") (class "Default")
      (node (ref "U1") (pin "A4") (pinfunction "PE0/TIM4_ETR/FSMC_NBL0/DCMI_D2/EVENTOUT_A4") (pintype "passive"))
    )
    (net (code "117") (name "unconnected-(U1B-PE1{slash}FSMC_NBL1{slash}DCMI_D3{slash}EVENTOUT-PadA3)") (class "Default")
      (node (ref "U1") (pin "A3") (pinfunction "PE1/FSMC_NBL1/DCMI_D3/EVENTOUT_A3") (pintype "passive"))
    )
    (net (code "118") (name "unconnected-(U1B-PE2{slash}TRACECLK{slash}FSMC_A23{slash}ETH_MII_TXD3{slash}EVENTOUT-PadA2)") (class "Default")
      (node (ref "U1") (pin "A2") (pinfunction "PE2/TRACECLK/FSMC_A23/ETH_MII_TXD3/EVENTOUT_A2") (pintype "passive"))
    )
    (net (code "119") (name "unconnected-(U1B-PE3{slash}TRACED0{slash}FSMC_A19{slash}EVENTOUT-PadA1)") (class "Default")
      (node (ref "U1") (pin "A1") (pinfunction "PE3/TRACED0/FSMC_A19/EVENTOUT_A1") (pintype "passive"))
    )
    (net (code "120") (name "unconnected-(U1B-PE4{slash}TRACED1{slash}FSMC_A20{slash}DCMI_D4{slash}EVENTOUT-PadB1)") (class "Default")
      (node (ref "U1") (pin "B1") (pinfunction "PE4/TRACED1/FSMC_A20/DCMI_D4/EVENTOUT_B1") (pintype "passive"))
    )
    (net (code "121") (name "unconnected-(U1B-PE5{slash}TRACED2{slash}FSMC_A21{slash}TIM9_CH1{slash}DCMI_D6{slash}EVENTOUT-PadB2)") (class "Default")
      (node (ref "U1") (pin "B2") (pinfunction "PE5/TRACED2/FSMC_A21/TIM9_CH1/DCMI_D6/EVENTOUT_B2") (pintype "passive"))
    )
    (net (code "122") (name "unconnected-(U1B-PE6{slash}TRACED3{slash}FSMC_A22{slash}TIM9_CH2{slash}DCMI_D7{slash}EVENTOUT-PadB3)") (class "Default")
      (node (ref "U1") (pin "B3") (pinfunction "PE6/TRACED3/FSMC_A22/TIM9_CH2/DCMI_D7/EVENTOUT_B3") (pintype "passive"))
    )
    (net (code "123") (name "unconnected-(U1B-PE7{slash}FSMC_D4{slash}TIM1_ETR{slash}EVENTOUT-PadR8)") (class "Default")
      (node (ref "U1") (pin "R8") (pinfunction "PE7/FSMC_D4/TIM1_ETR/EVENTOUT_R8") (pintype "passive"))
    )
    (net (code "124") (name "unconnected-(U1B-PE8{slash}FSMC_D5{slash}TIM1_CH1N{slash}EVENTOUT-PadP8)") (class "Default")
      (node (ref "U1") (pin "P8") (pinfunction "PE8/FSMC_D5/TIM1_CH1N/EVENTOUT_P8") (pintype "passive"))
    )
    (net (code "125") (name "unconnected-(U1B-PE10{slash}FSMC_D7{slash}TIM1_CH2N{slash}EVENTOUT-PadR9)") (class "Default")
      (node (ref "U1") (pin "R9") (pinfunction "PE10/FSMC_D7/TIM1_CH2N/EVENTOUT_R9") (pintype "passive"))
    )
    (net (code "126") (name "unconnected-(U1B-PE12{slash}FSMC_D9{slash}TIM1_CH3N{slash}EVENTOUT-PadR10)") (class "Default")
      (node (ref "U1") (pin "R10") (pinfunction "PE12/FSMC_D9/TIM1_CH3N/EVENTOUT_R10") (pintype "passive"))
    )
    (net (code "127") (name "unconnected-(U1B-PE15{slash}FSMC_D12{slash}TIM1_BKIN{slash}EVENTOUT-PadR11)") (class "Default")
      (node (ref "U1") (pin "R11") (pinfunction "PE15/FSMC_D12/TIM1_BKIN/EVENTOUT_R11") (pintype "passive"))
    )
    (net (code "128") (name "unconnected-(U1B-PF0{slash}FSMC_A0{slash}I2C2_SDA{slash}EVENTOUT-PadE2)") (class "Default")
      (node (ref "U1") (pin "E2") (pinfunction "PF0/FSMC_A0/I2C2_SDA/EVENTOUT_E2") (pintype "passive"))
    )
    (net (code "129") (name "unconnected-(U1B-PF2{slash}FSMC_A2{slash}I2C2_SMBA{slash}EVENTOUT-PadH2)") (class "Default")
      (node (ref "U1") (pin "H2") (pinfunction "PF2/FSMC_A2/I2C2_SMBA/EVENTOUT_H2") (pintype "passive"))
    )
    (net (code "130") (name "unconnected-(U1B-PF3{slash}FSMC_A3{slash}EVENTOUT{slash}ADC3_IN9-PadJ2)") (class "Default")
      (node (ref "U1") (pin "J2") (pinfunction "PF3/FSMC_A3/EVENTOUT/ADC3_IN9_J2") (pintype "passive"))
    )
    (net (code "131") (name "unconnected-(U1B-PF4{slash}FSMC_A4{slash}EVENTOUT{slash}ADC3_IN14-PadJ3)") (class "Default")
      (node (ref "U1") (pin "J3") (pinfunction "PF4/FSMC_A4/EVENTOUT/ADC3_IN14_J3") (pintype "passive"))
    )
    (net (code "132") (name "unconnected-(U1B-PF10{slash}FSMC_INTR{slash}EVENTOUT{slash}ADC3_IN8-PadL1)") (class "Default")
      (node (ref "U1") (pin "L1") (pinfunction "PF10/FSMC_INTR/EVENTOUT/ADC3_IN8_L1") (pintype "passive"))
    )
    (net (code "133") (name "unconnected-(U1B-PF11{slash}DCMI_12{slash}EVENTOUT-PadR6)") (class "Default")
      (node (ref "U1") (pin "R6") (pinfunction "PF11/DCMI_12/EVENTOUT_R6") (pintype "passive"))
    )
    (net (code "134") (name "unconnected-(U1B-PF12{slash}FSMC_A6{slash}EVENTOUT-PadP6)") (class "Default")
      (node (ref "U1") (pin "P6") (pinfunction "PF12/FSMC_A6/EVENTOUT_P6") (pintype "passive"))
    )
    (net (code "135") (name "unconnected-(U1B-PF13{slash}FSMC_A7{slash}EVENTOUT-PadN6)") (class "Default")
      (node (ref "U1") (pin "N6") (pinfunction "PF13/FSMC_A7/EVENTOUT_N6") (pintype "passive"))
    )
    (net (code "136") (name "unconnected-(U1C-PG8{slash}USART6_RTS{slash}ETH_PPS_OUT{slash}EVENTOUT-PadH14)") (class "Default")
      (node (ref "U1") (pin "H14") (pinfunction "PG8/USART6_RTS/ETH_PPS_OUT/EVENTOUT_H14") (pintype "passive"))
    )
    (net (code "137") (name "unconnected-(U1C-PG12{slash}FSMC_NE4{slash}USART6_RTS{slash}EVENTOUT-PadB8)") (class "Default")
      (node (ref "U1") (pin "B8") (pinfunction "PG12/FSMC_NE4/USART6_RTS/EVENTOUT_B8") (pintype "passive"))
    )
    (net (code "138") (name "unconnected-(U1C-PG13{slash}FSMC_A24{slash}USART6_CTS{slash}ETH_MII_TXD0{slash}ETH_RMII_TXD0{slash}EVENTOUT-PadA8)") (class "Default")
      (node (ref "U1") (pin "A8") (pinfunction "PG13/FSMC_A24/USART6_CTS/ETH_MII_TXD0/ETH_RMII_TXD0/EVENTOUT_A8") (pintype "passive"))
    )
    (net (code "139") (name "unconnected-(U1C-PG14{slash}FSMC_A25{slash}USART6_TX{slash}ETH_MII_TXD1{slash}ETH_RMII_TXD1{slash}EVENTOUT-PadA7)") (class "Default")
      (node (ref "U1") (pin "A7") (pinfunction "PG14/FSMC_A25/USART6_TX/ETH_MII_TXD1/ETH_RMII_TXD1/EVENTOUT_A7") (pintype "passive"))
    )
    (net (code "140") (name "unconnected-(U1C-PG15{slash}USART6_CTS{slash}DCMI_D13{slash}EVENTOUT-PadB7)") (class "Default")
      (node (ref "U1") (pin "B7") (pinfunction "PG15/USART6_CTS/DCMI_D13/EVENTOUT_B7") (pintype "passive"))
    )
    (net (code "141") (name "unconnected-(U1C-PH2{slash}ETH_MII_CRS{slash}EVENTOUT-PadF4)") (class "Default")
      (node (ref "U1") (pin "F4") (pinfunction "PH2/ETH_MII_CRS/EVENTOUT_F4") (pintype "passive"))
    )
    (net (code "142") (name "unconnected-(U1C-PH3{slash}ETH_MII_COL{slash}EVENTOUT-PadG4)") (class "Default")
      (node (ref "U1") (pin "G4") (pinfunction "PH3/ETH_MII_COL/EVENTOUT_G4") (pintype "passive"))
    )
    (net (code "143") (name "unconnected-(U1C-PH6{slash}I2C2_SMBA{slash}TIM12_CH1{slash}ETH_MII_RXD2{slash}EVENTOUT-PadM11)") (class "Default")
      (node (ref "U1") (pin "M11") (pinfunction "PH6/I2C2_SMBA/TIM12_CH1/ETH_MII_RXD2/EVENTOUT_M11") (pintype "passive"))
    )
    (net (code "144") (name "unconnected-(U1C-PH9{slash}I2C3_SMBA{slash}TIM12_CH2{slash}DCMI_D0{slash}EVENTOUT-PadM13)") (class "Default")
      (node (ref "U1") (pin "M13") (pinfunction "PH9/I2C3_SMBA/TIM12_CH2/DCMI_D0/EVENTOUT_M13") (pintype "passive"))
    )
    (net (code "145") (name "unconnected-(U1C-PH13{slash}TIM8_CH1N{slash}CAN1_TX{slash}EVENTOUT-PadE12)") (class "Default")
      (node (ref "U1") (pin "E12") (pinfunction "PH13/TIM8_CH1N/CAN1_TX/EVENTOUT_E12") (pintype "passive"))
    )
    (net (code "146") (name "unconnected-(U1C-PH14{slash}TIM8_CH2N{slash}DCMI_D4{slash}EVENTOUT-PadE13)") (class "Default")
      (node (ref "U1") (pin "E13") (pinfunction "PH14/TIM8_CH2N/DCMI_D4/EVENTOUT_E13") (pintype "passive"))
    )
    (net (code "147") (name "unconnected-(U1C-PH15{slash}TIM8_CH3N{slash}DCMI_D11{slash}EVENTOUT-PadD13)") (class "Default")
      (node (ref "U1") (pin "D13") (pinfunction "PH15/TIM8_CH3N/DCMI_D11/EVENTOUT_D13") (pintype "passive"))
    )
    (net (code "148") (name "unconnected-(U1C-PI1{slash}SPI2_SCK{slash}I2S2_CK{slash}DCMI_D8{slash}EVENTOUT-PadD14)") (class "Default")
      (node (ref "U1") (pin "D14") (pinfunction "PI1/SPI2_SCK/I2S2_CK/DCMI_D8/EVENTOUT_D14") (pintype "passive"))
    )
    (net (code "149") (name "unconnected-(U1C-PI3{slash}TIM8_ETR{slash}SPI2_MOSI{slash}I2S2_SD{slash}DCMI_D10{slash}EVENTOUT-PadC13)") (class "Default")
      (node (ref "U1") (pin "C13") (pinfunction "PI3/TIM8_ETR/SPI2_MOSI/I2S2_SD/DCMI_D10/EVENTOUT_C13") (pintype "passive"))
    )
    (net (code "150") (name "unconnected-(U1C-PI4{slash}TIM8_BKIN{slash}DCMI_D5{slash}EVENTOUT-PadD4)") (class "Default")
      (node (ref "U1") (pin "D4") (pinfunction "PI4/TIM8_BKIN/DCMI_D5/EVENTOUT_D4") (pintype "passive"))
    )
    (net (code "151") (name "unconnected-(U1C-PI8{slash}EVENTOUT{slash}RTC_AF2-PadD2)") (class "Default")
      (node (ref "U1") (pin "D2") (pinfunction "PI8/EVENTOUT/RTC_AF2_D2") (pintype "passive"))
    )
    (net (code "152") (name "unconnected-(U1C-PI9{slash}CAN1_RX{slash}EVENTOUT-PadD3)") (class "Default")
      (node (ref "U1") (pin "D3") (pinfunction "PI9/CAN1_RX/EVENTOUT_D3") (pintype "passive"))
    )
    (net (code "153") (name "unconnected-(U1C-PI10{slash}ETH_MII_RX_ER{slash}EVENTOUT-PadE3)") (class "Default")
      (node (ref "U1") (pin "E3") (pinfunction "PI10/ETH_MII_RX_ER/EVENTOUT_E3") (pintype "passive"))
    )
    (net (code "154") (name "unconnected-(U1C-PI11{slash}OTG_HS_ULPI_DIR{slash}EVENTOUT-PadE4)") (class "Default")
      (node (ref "U1") (pin "E4") (pinfunction "PI11/OTG_HS_ULPI_DIR/EVENTOUT_E4") (pintype "passive"))
    )
  )
)
